# finch_pack.net
KiCad netlist of a schematic drawn in EAGLE
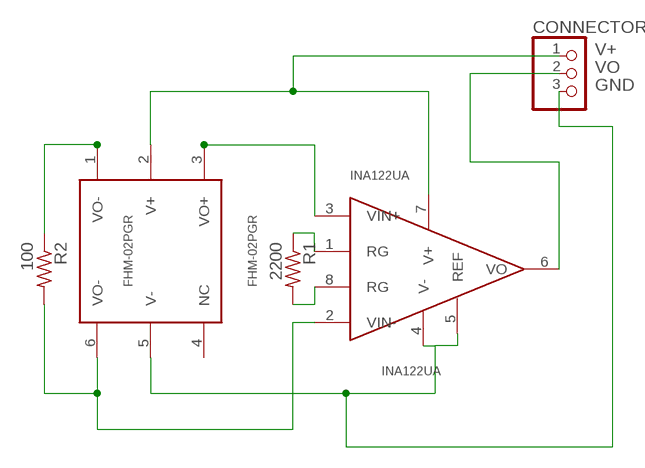
[diagram p0: schematic, sheet 1]

(export (version "E")
  (design (tool "Eeschema 10.0.6"))
  (components
    (comp (ref "CONNECTOR")
      (value "PINHD-1X3")
      (footprint "eagle-import:1X03")
      (libsource (lib "eagle-import") (part "PINHD-1X3"))
    )
    (comp (ref "FHM-02PGR")
      (value "FHM-02PGR")
      (footprint "eagle-import:FHM-02PGR")
      (libsource (lib "eagle-import") (part "FHM-02PGR"))
    )
    (comp (ref "INA122UA")
      (value "INA122UA")
      (footprint "eagle-import:INA122UA")
      (libsource (lib "eagle-import") (part "INA122UA"))
    )
    (comp (ref "R1")
      (value "2200")
      (footprint "eagle-import:0309_10")
      (libsource (lib "eagle-import") (part "R-US_0309/10"))
    )
    (comp (ref "R2")
      (value "100")
      (footprint "eagle-import:0309_10")
      (libsource (lib "eagle-import") (part "R-US_0309/10"))
    )
  )
  (nets
    (net (code "1") (name "/GND") (class "Default")
      (node (ref "CONNECTOR") (pin "3") (pinfunction "3_3") (pintype "passive"))
      (node (ref "FHM-02PGR") (pin "5") (pinfunction "V-_5") (pintype "bidirectional"))
      (node (ref "INA122UA") (pin "4") (pinfunction "V-_4") (pintype "bidirectional"))
      (node (ref "INA122UA") (pin "5") (pinfunction "REF_5") (pintype "bidirectional"))
    )
    (net (code "2") (name "/V+") (class "Default")
      (node (ref "CONNECTOR") (pin "1") (pinfunction "1_1") (pintype "passive"))
      (node (ref "FHM-02PGR") (pin "2") (pinfunction "V+_2") (pintype "bidirectional"))
      (node (ref "INA122UA") (pin "7") (pinfunction "V+_7") (pintype "bidirectional"))
    )
    (net (code "3") (name "/VO") (class "Default")
      (node (ref "CONNECTOR") (pin "2") (pinfunction "2_2") (pintype "passive"))
      (node (ref "INA122UA") (pin "6") (pinfunction "VO_6") (pintype "bidirectional"))
    )
    (net (code "4") (name "Net-(FHM-02PGR-VO+)") (class "Default")
      (node (ref "FHM-02PGR") (pin "3") (pinfunction "VO+_3") (pintype "bidirectional"))
      (node (ref "INA122UA") (pin "3") (pinfunction "VIN+_3") (pintype "bidirectional"))
    )
    (net (code "5") (name "Net-(FHM-02PGR-VO--Pad1)") (class "Default")
      (node (ref "FHM-02PGR") (pin "1") (pinfunction "VO-_1") (pintype "bidirectional"))
      (node (ref "R2") (pin "1") (pinfunction "1_1") (pintype "passive"))
    )
    (net (code "6") (name "Net-(INA122UA-RG-Pad1)") (class "Default")
      (node (ref "INA122UA") (pin "1") (pinfunction "RG_1") (pintype "bidirectional"))
      (node (ref "R1") (pin "1") (pinfunction "1_1") (pintype "passive"))
    )
    (net (code "7") (name "Net-(INA122UA-RG-Pad8)") (class "Default")
      (node (ref "INA122UA") (pin "8") (pinfunction "RG_8") (pintype "bidirectional"))
      (node (ref "R1") (pin "2") (pinfunction "2_2") (pintype "passive"))
    )
    (net (code "8") (name "Net-(INA122UA-VIN-)") (class "Default")
      (node (ref "FHM-02PGR") (pin "6") (pinfunction "VO-_6") (pintype "bidirectional"))
      (node (ref "INA122UA") (pin "2") (pinfunction "VIN-_2") (pintype "bidirectional"))
      (node (ref "R2") (pin "2") (pinfunction "2_2") (pintype "passive"))
    )
    (net (code "9") (name "unconnected-(FHM-02PGR-NC-Pad4)") (class "Default")
      (node (ref "FHM-02PGR") (pin "4") (pinfunction "NC_4") (pintype "bidirectional"))
    )
  )
)
